# 02-USER_IO_STATUS.net
KiCad netlist of a schematic drawn in Altium Designer
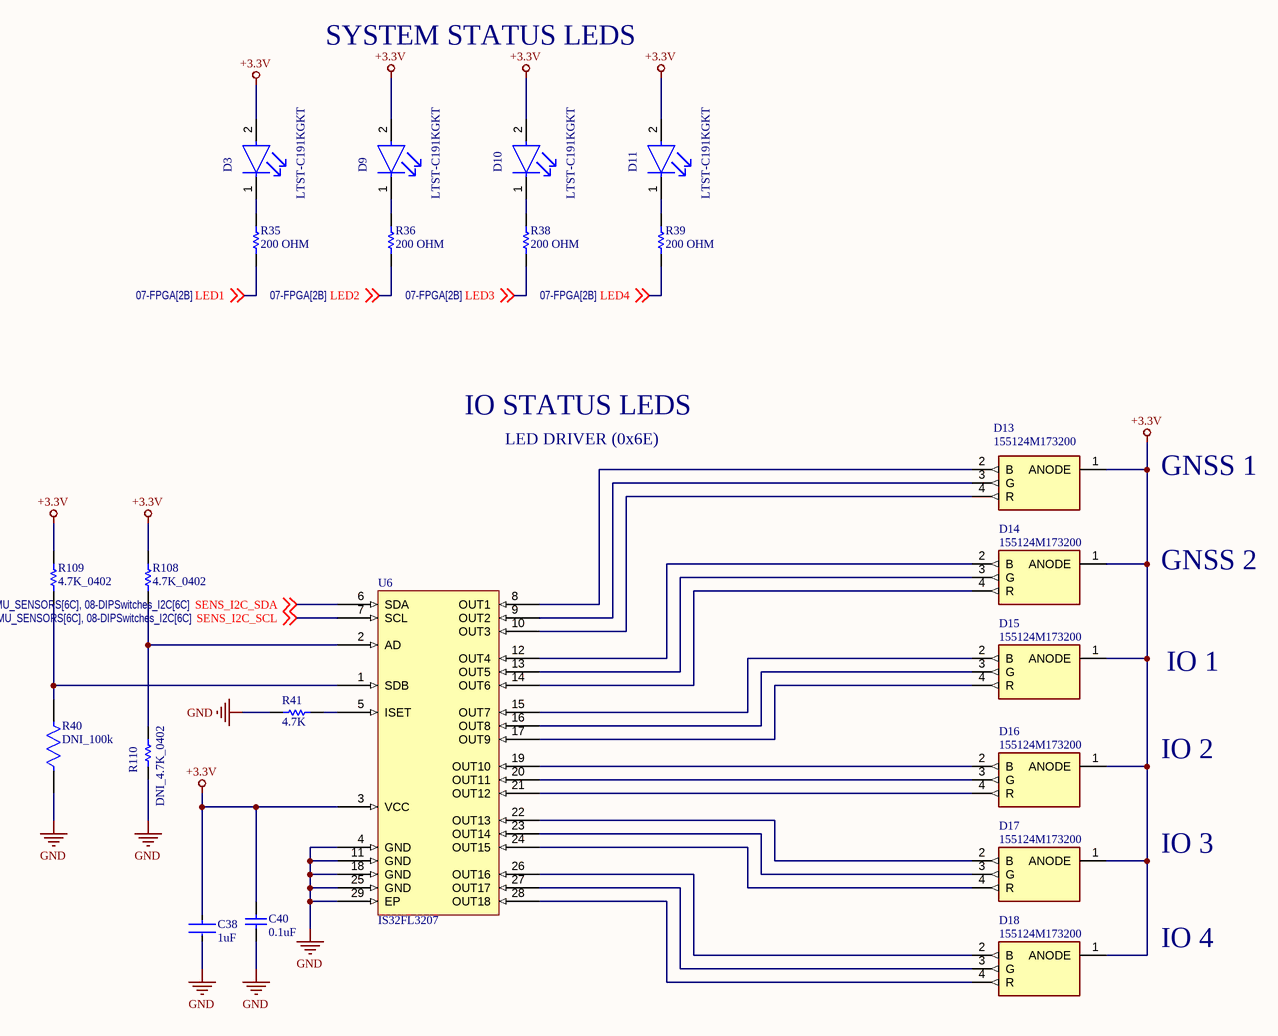
[diagram p0: 02-USER_IO_STATUS.SchDoc]

(export (version "E")
  (design (tool "Eeschema 10.0.6"))
  (components
    (comp (ref "C38")
      (value "1uF")
      (footprint "FP-C0603C105K3PACTU-MFG")
      (description "CAP CER 1UF 25V X5R 0603")
      (fields (field (name "VOLTAGE") "25V") (field (name "TOLERANCE") "10%"))
      (libsource (lib "Altium Content Vault") (part "e9c51b7dd13d4faca003ae77663ab08"))
    )
    (comp (ref "C40")
      (value "0.1uF")
      (footprint "CAPC1608X87X45ML20T05")
      (description "C0603X104K5RACAUTO")
      (fields (field (name "MANUFACTURER") "Kemet"))
      (libsource (lib "Altium Content Vault") (part "CAP"))
    )
    (comp (ref "D3")
      (value "LTST-C191KGKT")
      (footprint "FP-LTST-C191KGKT-MFG")
      (description "LED GREEN CLEAR SMD")
      (libsource (lib "Altium Content Vault") (part "8706943c75ba83719d021d2fdc84c58"))
    )
    (comp (ref "D9")
      (value "LTST-C191KGKT")
      (footprint "FP-LTST-C191KGKT-MFG")
      (description "LED GREEN CLEAR SMD")
      (libsource (lib "Altium Content Vault") (part "8706943c75ba83719d021d2fdc84c58"))
    )
    (comp (ref "D10")
      (value "LTST-C191KGKT")
      (footprint "FP-LTST-C191KGKT-MFG")
      (description "LED GREEN CLEAR SMD")
      (libsource (lib "Altium Content Vault") (part "8706943c75ba83719d021d2fdc84c58"))
    )
    (comp (ref "D11")
      (value "LTST-C191KGKT")
      (footprint "FP-LTST-C191KGKT-MFG")
      (description "LED GREEN CLEAR SMD")
      (libsource (lib "Altium Content Vault") (part "8706943c75ba83719d021d2fdc84c58"))
    )
    (comp (ref "D13")
      (value "155124M173200")
      (footprint "SamacSys:155124M173200")
      (description "LED (Multiple)")
      (fields (field (name "MOUSER PART NUMBER") "710-155124M173200"))
      (libsource (lib "SamacSys") (part "155124M173200"))
    )
    (comp (ref "D14")
      (value "155124M173200")
      (footprint "SamacSys:155124M173200")
      (description "LED (Multiple)")
      (fields (field (name "MOUSER PART NUMBER") "710-155124M173200"))
      (libsource (lib "SamacSys") (part "155124M173200"))
    )
    (comp (ref "D15")
      (value "155124M173200")
      (footprint "SamacSys:155124M173200")
      (description "LED (Multiple)")
      (fields (field (name "MOUSER PART NUMBER") "710-155124M173200"))
      (libsource (lib "SamacSys") (part "155124M173200"))
    )
    (comp (ref "D16")
      (value "155124M173200")
      (footprint "SamacSys:155124M173200")
      (description "LED (Multiple)")
      (fields (field (name "MOUSER PART NUMBER") "710-155124M173200"))
      (libsource (lib "SamacSys") (part "155124M173200"))
    )
    (comp (ref "D17")
      (value "155124M173200")
      (footprint "SamacSys:155124M173200")
      (description "LED (Multiple)")
      (fields (field (name "MOUSER PART NUMBER") "710-155124M173200"))
      (libsource (lib "SamacSys") (part "155124M173200"))
    )
    (comp (ref "D18")
      (value "155124M173200")
      (footprint "SamacSys:155124M173200")
      (description "LED (Multiple)")
      (fields (field (name "MOUSER PART NUMBER") "710-155124M173200"))
      (libsource (lib "SamacSys") (part "155124M173200"))
    )
    (comp (ref "R35")
      (value "200 OHM")
      (footprint "RESC1608X55X30NL15T15")
      (description "ERJ-3EKF2000V")
      (fields (field (name "MANUFACTURER") "Panasonic"))
      (libsource (lib "Altium Content Vault") (part "RES"))
    )
    (comp (ref "R36")
      (value "200 OHM")
      (footprint "RESC1608X55X30NL15T15")
      (description "ERJ-3EKF2000V")
      (fields (field (name "MANUFACTURER") "Panasonic"))
      (libsource (lib "Altium Content Vault") (part "RES"))
    )
    (comp (ref "R38")
      (value "200 OHM")
      (footprint "RESC1608X55X30NL15T15")
      (description "ERJ-3EKF2000V")
      (fields (field (name "MANUFACTURER") "Panasonic"))
      (libsource (lib "Altium Content Vault") (part "RES"))
    )
    (comp (ref "R39")
      (value "200 OHM")
      (footprint "RESC1608X55X30NL15T15")
      (description "ERJ-3EKF2000V")
      (fields (field (name "MANUFACTURER") "Panasonic"))
      (libsource (lib "Altium Content Vault") (part "RES"))
    )
    (comp (ref "R40")
      (value "DNI_100k")
      (footprint "FP-RC0603-0_55-MFG")
      (description "RES SMD 100K OHM 1% 1/10W 0603")
      (fields (field (name "TOLERANCE") "1%"))
      (libsource (lib "Altium Content Vault") (part "1029c3af85768c4190bb7ad29bc67b5"))
    )
    (comp (ref "R41")
      (value "4.7K")
      (footprint "RESC1608X55X30NL15T15")
      (fields (field (name "TOLERANCE") "5%"))
      (libsource (lib "Altium Content Vault") (part "RES-2"))
    )
    (comp (ref "R108")
      (value "4.7K_0402")
      (footprint "RESC1005X40X25LL05T05")
      (description "Chip Resistor, 4.7 KOhm, +/- 1%, 0.1 W, -55 to 155 degC, 0402 (1005 Metric), RoHS, Tape and Reel")
      (fields (field (name "TOLERANCE") "1%") (field (name "PARTNUMBER") "ERJ-2RKF4701X"))
      (libsource (lib "Altium Content Vault") (part "RES-2"))
    )
    (comp (ref "R109")
      (value "4.7K_0402")
      (footprint "RESC1005X40X25LL05T05")
      (description "Chip Resistor, 4.7 KOhm, +/- 1%, 0.1 W, -55 to 155 degC, 0402 (1005 Metric), RoHS, Tape and Reel")
      (fields (field (name "TOLERANCE") "1%") (field (name "PARTNUMBER") "ERJ-2RKF4701X"))
      (libsource (lib "Altium Content Vault") (part "RES-2"))
    )
    (comp (ref "R110")
      (value "DNI_4.7K_0402")
      (footprint "RESC1005X40X25LL05T05")
      (description "Chip Resistor, 4.7 KOhm, +/- 1%, 0.1 W, -55 to 155 degC, 0402 (1005 Metric), RoHS, Tape and Reel")
      (fields (field (name "TOLERANCE") "1%") (field (name "PARTNUMBER") "ERJ-2RKF4701X"))
      (libsource (lib "Altium Content Vault") (part "RES-2"))
    )
    (comp (ref "U6")
      (value "IS32FL3207")
      (footprint "IS32FL3207")
      (libsource (lib "IS32FL3207") (part "IS32FL3207"))
    )
  )
  (nets
    (net (code "1") (name "+3.3V") (class "Default")
      (node (ref "C38") (pin "1") (pinfunction "1_1") (pintype "passive"))
      (node (ref "C40") (pin "2") (pinfunction "2_2") (pintype "passive"))
      (node (ref "D10") (pin "2") (pinfunction "A_2") (pintype "passive"))
      (node (ref "D11") (pin "2") (pinfunction "A_2") (pintype "passive"))
      (node (ref "D13") (pin "1") (pinfunction "ANODE_1") (pintype "power_in"))
      (node (ref "D14") (pin "1") (pinfunction "ANODE_1") (pintype "power_in"))
      (node (ref "D15") (pin "1") (pinfunction "ANODE_1") (pintype "power_in"))
      (node (ref "D16") (pin "1") (pinfunction "ANODE_1") (pintype "power_in"))
      (node (ref "D17") (pin "1") (pinfunction "ANODE_1") (pintype "power_in"))
      (node (ref "D18") (pin "1") (pinfunction "ANODE_1") (pintype "power_in"))
      (node (ref "D3") (pin "2") (pinfunction "A_2") (pintype "passive"))
      (node (ref "D9") (pin "2") (pinfunction "A_2") (pintype "passive"))
      (node (ref "R108") (pin "1") (pinfunction "1_1") (pintype "passive"))
      (node (ref "R109") (pin "1") (pinfunction "1_1") (pintype "passive"))
      (node (ref "U6") (pin "3") (pinfunction "VCC_3") (pintype "input"))
    )
    (net (code "2") (name "GND") (class "Default")
      (node (ref "C38") (pin "2") (pinfunction "2_2") (pintype "passive"))
      (node (ref "C40") (pin "1") (pinfunction "1_1") (pintype "passive"))
      (node (ref "R110") (pin "2") (pinfunction "2_2") (pintype "passive"))
      (node (ref "R40") (pin "1") (pinfunction "1_1") (pintype "passive"))
      (node (ref "R41") (pin "1") (pinfunction "1_1") (pintype "passive"))
      (node (ref "U6") (pin "11") (pinfunction "GND_11") (pintype "input"))
      (node (ref "U6") (pin "18") (pinfunction "GND_18") (pintype "input"))
      (node (ref "U6") (pin "25") (pinfunction "GND_25") (pintype "input"))
      (node (ref "U6") (pin "29") (pinfunction "EP_29") (pintype "input"))
      (node (ref "U6") (pin "4") (pinfunction "GND_4") (pintype "input"))
    )
    (net (code "3") (name "LED1") (class "Default")
      (node (ref "R35") (pin "1") (pinfunction "1_1") (pintype "passive"))
    )
    (net (code "4") (name "LED2") (class "Default")
      (node (ref "R36") (pin "1") (pinfunction "1_1") (pintype "passive"))
    )
    (net (code "5") (name "LED3") (class "Default")
      (node (ref "R38") (pin "1") (pinfunction "1_1") (pintype "passive"))
    )
    (net (code "6") (name "LED4") (class "Default")
      (node (ref "R39") (pin "1") (pinfunction "1_1") (pintype "passive"))
    )
    (net (code "7") (name "Net-(D3-C)") (class "Default")
      (node (ref "D3") (pin "1") (pinfunction "C_1") (pintype "passive"))
      (node (ref "R35") (pin "2") (pinfunction "2_2") (pintype "passive"))
    )
    (net (code "8") (name "Net-(D9-C)") (class "Default")
      (node (ref "D9") (pin "1") (pinfunction "C_1") (pintype "passive"))
      (node (ref "R36") (pin "2") (pinfunction "2_2") (pintype "passive"))
    )
    (net (code "9") (name "Net-(D10-C)") (class "Default")
      (node (ref "D10") (pin "1") (pinfunction "C_1") (pintype "passive"))
      (node (ref "R38") (pin "2") (pinfunction "2_2") (pintype "passive"))
    )
    (net (code "10") (name "Net-(D11-C)") (class "Default")
      (node (ref "D11") (pin "1") (pinfunction "C_1") (pintype "passive"))
      (node (ref "R39") (pin "2") (pinfunction "2_2") (pintype "passive"))
    )
    (net (code "11") (name "Net-(D13-B)") (class "Default")
      (node (ref "D13") (pin "2") (pinfunction "B_2") (pintype "output"))
      (node (ref "U6") (pin "8") (pinfunction "OUT1_8") (pintype "input"))
    )
    (net (code "12") (name "Net-(D13-G)") (class "Default")
      (node (ref "D13") (pin "3") (pinfunction "G_3") (pintype "output"))
      (node (ref "U6") (pin "9") (pinfunction "OUT2_9") (pintype "input"))
    )
    (net (code "13") (name "Net-(D13-R)") (class "Default")
      (node (ref "D13") (pin "4") (pinfunction "R_4") (pintype "output"))
      (node (ref "U6") (pin "10") (pinfunction "OUT3_10") (pintype "input"))
    )
    (net (code "14") (name "Net-(D14-B)") (class "Default")
      (node (ref "D14") (pin "2") (pinfunction "B_2") (pintype "output"))
      (node (ref "U6") (pin "12") (pinfunction "OUT4_12") (pintype "input"))
    )
    (net (code "15") (name "Net-(D14-G)") (class "Default")
      (node (ref "D14") (pin "3") (pinfunction "G_3") (pintype "output"))
      (node (ref "U6") (pin "13") (pinfunction "OUT5_13") (pintype "input"))
    )
    (net (code "16") (name "Net-(D14-R)") (class "Default")
      (node (ref "D14") (pin "4") (pinfunction "R_4") (pintype "output"))
      (node (ref "U6") (pin "14") (pinfunction "OUT6_14") (pintype "input"))
    )
    (net (code "17") (name "Net-(D15-B)") (class "Default")
      (node (ref "D15") (pin "2") (pinfunction "B_2") (pintype "output"))
      (node (ref "U6") (pin "15") (pinfunction "OUT7_15") (pintype "input"))
    )
    (net (code "18") (name "Net-(D15-G)") (class "Default")
      (node (ref "D15") (pin "3") (pinfunction "G_3") (pintype "output"))
      (node (ref "U6") (pin "16") (pinfunction "OUT8_16") (pintype "input"))
    )
    (net (code "19") (name "Net-(D15-R)") (class "Default")
      (node (ref "D15") (pin "4") (pinfunction "R_4") (pintype "output"))
      (node (ref "U6") (pin "17") (pinfunction "OUT9_17") (pintype "input"))
    )
    (net (code "20") (name "Net-(D16-B)") (class "Default")
      (node (ref "D16") (pin "2") (pinfunction "B_2") (pintype "output"))
      (node (ref "U6") (pin "19") (pinfunction "OUT10_19") (pintype "input"))
    )
    (net (code "21") (name "Net-(D16-G)") (class "Default")
      (node (ref "D16") (pin "3") (pinfunction "G_3") (pintype "output"))
      (node (ref "U6") (pin "20") (pinfunction "OUT11_20") (pintype "input"))
    )
    (net (code "22") (name "Net-(D16-R)") (class "Default")
      (node (ref "D16") (pin "4") (pinfunction "R_4") (pintype "output"))
      (node (ref "U6") (pin "21") (pinfunction "OUT12_21") (pintype "input"))
    )
    (net (code "23") (name "Net-(D17-B)") (class "Default")
      (node (ref "D17") (pin "2") (pinfunction "B_2") (pintype "output"))
      (node (ref "U6") (pin "22") (pinfunction "OUT13_22") (pintype "input"))
    )
    (net (code "24") (name "Net-(D17-G)") (class "Default")
      (node (ref "D17") (pin "3") (pinfunction "G_3") (pintype "output"))
      (node (ref "U6") (pin "23") (pinfunction "OUT14_23") (pintype "input"))
    )
    (net (code "25") (name "Net-(D17-R)") (class "Default")
      (node (ref "D17") (pin "4") (pinfunction "R_4") (pintype "output"))
      (node (ref "U6") (pin "24") (pinfunction "OUT15_24") (pintype "input"))
    )
    (net (code "26") (name "Net-(D18-B)") (class "Default")
      (node (ref "D18") (pin "2") (pinfunction "B_2") (pintype "output"))
      (node (ref "U6") (pin "26") (pinfunction "OUT16_26") (pintype "input"))
    )
    (net (code "27") (name "Net-(D18-G)") (class "Default")
      (node (ref "D18") (pin "3") (pinfunction "G_3") (pintype "output"))
      (node (ref "U6") (pin "27") (pinfunction "OUT17_27") (pintype "input"))
    )
    (net (code "28") (name "Net-(D18-R)") (class "Default")
      (node (ref "D18") (pin "4") (pinfunction "R_4") (pintype "output"))
      (node (ref "U6") (pin "28") (pinfunction "OUT18_28") (pintype "input"))
    )
    (net (code "29") (name "Net-(U6-AD)") (class "Default")
      (node (ref "R108") (pin "2") (pinfunction "2_2") (pintype "passive"))
      (node (ref "R110") (pin "1") (pinfunction "1_1") (pintype "passive"))
      (node (ref "U6") (pin "2") (pinfunction "AD_2") (pintype "input"))
    )
    (net (code "30") (name "Net-(U6-ISET)") (class "Default")
      (node (ref "R41") (pin "2") (pinfunction "2_2") (pintype "passive"))
      (node (ref "U6") (pin "5") (pinfunction "ISET_5") (pintype "input"))
    )
    (net (code "31") (name "Net-(U6-SDB)") (class "Default")
      (node (ref "R109") (pin "2") (pinfunction "2_2") (pintype "passive"))
      (node (ref "R40") (pin "2") (pinfunction "2_2") (pintype "passive"))
      (node (ref "U6") (pin "1") (pinfunction "SDB_1") (pintype "input"))
    )
    (net (code "32") (name "SENS_I2C_SCL") (class "Default")
      (node (ref "U6") (pin "7") (pinfunction "SCL_7") (pintype "input"))
    )
    (net (code "33") (name "SENS_I2C_SDA") (class "Default")
      (node (ref "U6") (pin "6") (pinfunction "SDA_6") (pintype "input"))
    )
  )
)
